# ARM_critter_v02.net
KiCad netlist of a schematic drawn in EAGLE
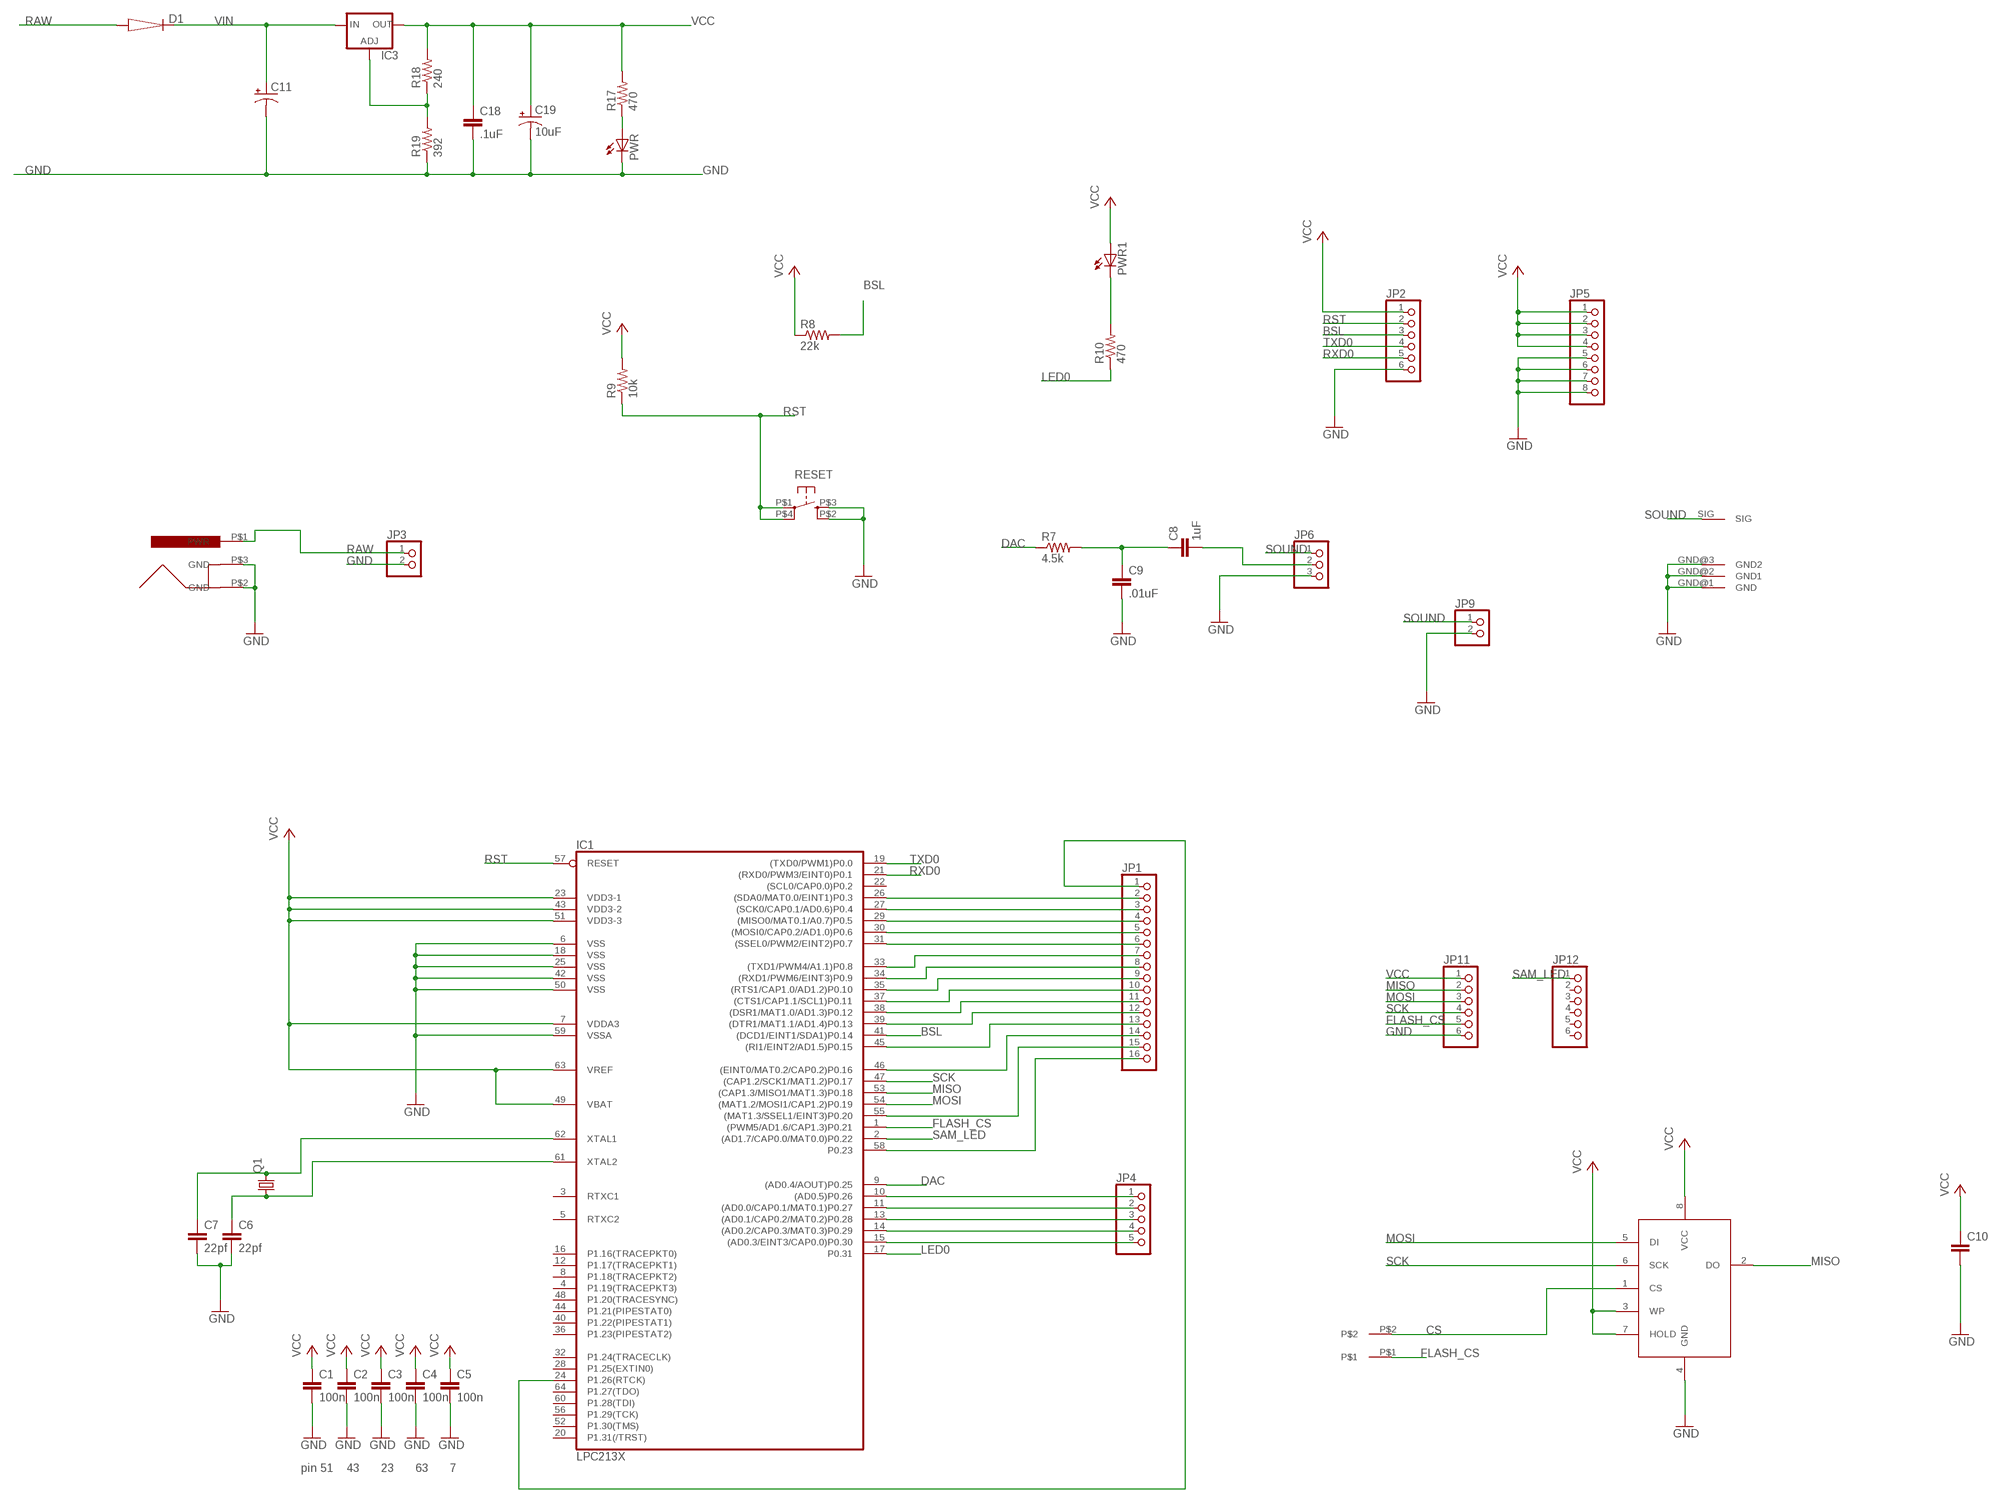
[diagram p0: schematic, sheet 1]

(export (version "E")
  (design (tool "Eeschema 10.0.6"))
  (components
    (comp (ref "C1")
      (value "100n")
      (footprint "eagle-import:C0603")
      (libsource (lib "eagle-import") (part "CAP0603"))
    )
    (comp (ref "C2")
      (value "100n")
      (footprint "eagle-import:C0603")
      (libsource (lib "eagle-import") (part "CAP0603"))
    )
    (comp (ref "C3")
      (value "100n")
      (footprint "eagle-import:C0603")
      (libsource (lib "eagle-import") (part "CAP0603"))
    )
    (comp (ref "C4")
      (value "100n")
      (footprint "eagle-import:C0603")
      (libsource (lib "eagle-import") (part "CAP0603"))
    )
    (comp (ref "C5")
      (value "100n")
      (footprint "eagle-import:C0603")
      (libsource (lib "eagle-import") (part "CAP0603"))
    )
    (comp (ref "C6")
      (value "22pf")
      (footprint "eagle-import:C0603")
      (libsource (lib "eagle-import") (part "CAP0603"))
    )
    (comp (ref "C7")
      (value "22pf")
      (footprint "eagle-import:C0603")
      (libsource (lib "eagle-import") (part "CAP0603"))
    )
    (comp (ref "C8")
      (value "1uF")
      (footprint "eagle-import:C0603")
      (libsource (lib "eagle-import") (part "CAP0603"))
    )
    (comp (ref "C9")
      (value ".01uF")
      (footprint "eagle-import:C0603")
      (libsource (lib "eagle-import") (part "CAP0603"))
    )
    (comp (ref "C10")
      (value "CAP0603")
      (footprint "eagle-import:C0603")
      (libsource (lib "eagle-import") (part "CAP0603"))
    )
    (comp (ref "C11")
      (value "CPOL-USE3.5-8")
      (footprint "eagle-import:E3,5-8")
      (libsource (lib "eagle-import") (part "CPOL-USE3.5-8"))
    )
    (comp (ref "C18")
      (value ".1uF")
      (footprint "eagle-import:C0603")
      (libsource (lib "eagle-import") (part "CAP0603"))
    )
    (comp (ref "C19")
      (value "10uF")
      (footprint "eagle-import:CPOL_1206")
      (libsource (lib "eagle-import") (part "CAP_POL1206"))
    )
    (comp (ref "D1")
      (value "DIODESMB")
      (footprint "eagle-import:SMB")
      (libsource (lib "eagle-import") (part "DIODESMB"))
    )
    (comp (ref "IC1")
      (value "LPC213X")
      (footprint "eagle-import:SQFP-S-10X10-64")
      (libsource (lib "eagle-import") (part "LPC213X"))
    )
    (comp (ref "IC3")
      (value "V_REG_FAN1117SOT223")
      (footprint "eagle-import:SOT223")
      (libsource (lib "eagle-import") (part "V_REG_FAN1117SOT223"))
    )
    (comp (ref "JP1")
      (value "PINHD-1X16")
      (footprint "eagle-import:1X16")
      (libsource (lib "eagle-import") (part "PINHD-1X16"))
    )
    (comp (ref "JP2")
      (value "PINHD-1X6")
      (footprint "eagle-import:1X06")
      (libsource (lib "eagle-import") (part "PINHD-1X6"))
    )
    (comp (ref "JP3")
      (value "PINHD-1X2")
      (footprint "eagle-import:1X02")
      (libsource (lib "eagle-import") (part "PINHD-1X2"))
    )
    (comp (ref "JP4")
      (value "PINHD-1X5")
      (footprint "eagle-import:1X05")
      (libsource (lib "eagle-import") (part "PINHD-1X5"))
    )
    (comp (ref "JP5")
      (value "PINHD-1X8")
      (footprint "eagle-import:1X08")
      (libsource (lib "eagle-import") (part "PINHD-1X8"))
    )
    (comp (ref "JP6")
      (value "PINHD-1X3")
      (footprint "eagle-import:1X03")
      (libsource (lib "eagle-import") (part "PINHD-1X3"))
    )
    (comp (ref "JP9")
      (value "PINHD-1X2")
      (footprint "eagle-import:1X02")
      (libsource (lib "eagle-import") (part "PINHD-1X2"))
    )
    (comp (ref "JP11")
      (value "PINHD-1X6")
      (footprint "eagle-import:1X06")
      (libsource (lib "eagle-import") (part "PINHD-1X6"))
    )
    (comp (ref "JP12")
      (value "PINHD-1X6")
      (footprint "eagle-import:1X06")
      (libsource (lib "eagle-import") (part "PINHD-1X6"))
    )
    (comp (ref "PWR")
      (value "LED1206")
      (footprint "eagle-import:CHIPLED_1206")
      (libsource (lib "eagle-import") (part "LED1206"))
    )
    (comp (ref "PWR1")
      (value "LED1206")
      (footprint "eagle-import:CHIPLED_1206")
      (libsource (lib "eagle-import") (part "LED1206"))
    )
    (comp (ref "Q1")
      (value "CRYSTALHC49UV")
      (footprint "eagle-import:HC49U-V")
      (libsource (lib "eagle-import") (part "CRYSTALHC49UV"))
    )
    (comp (ref "R7")
      (value "4.5k")
      (footprint "eagle-import:R0603")
      (libsource (lib "eagle-import") (part "RES0603"))
    )
    (comp (ref "R8")
      (value "22k")
      (footprint "eagle-import:R0603")
      (libsource (lib "eagle-import") (part "RES0603"))
    )
    (comp (ref "R9")
      (value "10k")
      (footprint "eagle-import:R0603")
      (libsource (lib "eagle-import") (part "RES0603"))
    )
    (comp (ref "R10")
      (value "470")
      (footprint "eagle-import:R0603")
      (libsource (lib "eagle-import") (part "RES0603"))
    )
    (comp (ref "R17")
      (value "470")
      (footprint "eagle-import:R0603")
      (libsource (lib "eagle-import") (part "RES0603"))
    )
    (comp (ref "R18")
      (value "240")
      (footprint "eagle-import:R0603")
      (libsource (lib "eagle-import") (part "RES0603"))
    )
    (comp (ref "R19")
      (value "392")
      (footprint "eagle-import:R0603")
      (libsource (lib "eagle-import") (part "RES0603"))
    )
    (comp (ref "RESET")
      (value "RESET_SWITCH")
      (footprint "eagle-import:TACTILE_SWITCH_SMD")
      (libsource (lib "eagle-import") (part "RESET_SWITCH"))
    )
    (comp (ref "U$1")
      (value "POWER_JACK")
      (footprint "eagle-import:POWER_JACK")
      (libsource (lib "eagle-import") (part "POWER_JACKTHRU-HOLE"))
    )
    (comp (ref "U$2")
      (value "M25PXX")
      (footprint "eagle-import:SO08")
      (libsource (lib "eagle-import") (part "M25PXX"))
    )
    (comp (ref "U$3")
      (value "JUMPER_SOL")
      (footprint "eagle-import:JUMPER_SOL")
      (libsource (lib "eagle-import") (part "JUMPER_SOL"))
    )
    (comp (ref "U$5")
      (value "PHONO_PLUG")
      (footprint "eagle-import:PHONO_PCB")
      (libsource (lib "eagle-import") (part "PHONO_PLUG"))
    )
  )
  (nets
    (net (code "1") (name "/BSL") (class "Default")
      (node (ref "IC1") (pin "41") (pinfunction "(DCD1/EINT1/SDA1)P0.14_41") (pintype "bidirectional"))
      (node (ref "JP2") (pin "3") (pinfunction "3_3") (pintype "passive"))
      (node (ref "R8") (pin "2") (pinfunction "2_2") (pintype "passive"))
    )
    (net (code "2") (name "/CS") (class "Default")
      (node (ref "U$2") (pin "1") (pinfunction "CS_1") (pintype "bidirectional"))
      (node (ref "U$3") (pin "P$2") (pinfunction "P$2_P$2") (pintype "bidirectional"))
    )
    (net (code "3") (name "/DAC") (class "Default")
      (node (ref "IC1") (pin "9") (pinfunction "(AD0.4/AOUT)P0.25_9") (pintype "bidirectional"))
      (node (ref "R7") (pin "1") (pinfunction "1_1") (pintype "passive"))
    )
    (net (code "4") (name "/FLASH_CS") (class "Default")
      (node (ref "IC1") (pin "1") (pinfunction "(PWM5/AD1.6/CAP1.3)P0.21_1") (pintype "bidirectional"))
      (node (ref "JP11") (pin "5") (pinfunction "5_5") (pintype "passive"))
      (node (ref "U$3") (pin "P$1") (pinfunction "P$1_P$1") (pintype "bidirectional"))
    )
    (net (code "5") (name "/LED0") (class "Default")
      (node (ref "IC1") (pin "17") (pinfunction "P0.31_17") (pintype "output"))
      (node (ref "R10") (pin "1") (pinfunction "1_1") (pintype "passive"))
    )
    (net (code "6") (name "/MISO") (class "Default")
      (node (ref "IC1") (pin "53") (pinfunction "(CAP1.3/MISO1/MAT1.3)P0.18_53") (pintype "bidirectional"))
      (node (ref "JP11") (pin "2") (pinfunction "2_2") (pintype "passive"))
      (node (ref "U$2") (pin "2") (pinfunction "DO_2") (pintype "bidirectional"))
    )
    (net (code "7") (name "/MOSI") (class "Default")
      (node (ref "IC1") (pin "54") (pinfunction "(MAT1.2/MOSI1/CAP1.2)P0.19_54") (pintype "bidirectional"))
      (node (ref "JP11") (pin "3") (pinfunction "3_3") (pintype "passive"))
      (node (ref "U$2") (pin "5") (pinfunction "DI_5") (pintype "bidirectional"))
    )
    (net (code "8") (name "/RAW") (class "Default")
      (node (ref "D1") (pin "2") (pinfunction "C_2") (pintype "passive"))
      (node (ref "JP3") (pin "1") (pinfunction "1_1") (pintype "passive"))
      (node (ref "U$1") (pin "P$1") (pinfunction "PWR_P$1") (pintype "bidirectional"))
    )
    (net (code "9") (name "/RST") (class "Default")
      (node (ref "IC1") (pin "57") (pinfunction "RESET_57") (pintype "input"))
      (node (ref "JP2") (pin "2") (pinfunction "2_2") (pintype "passive"))
      (node (ref "R9") (pin "1") (pinfunction "1_1") (pintype "passive"))
      (node (ref "RESET") (pin "P$1") (pinfunction "P_P$1") (pintype "passive"))
      (node (ref "RESET") (pin "P$4") (pinfunction "P1_P$4") (pintype "passive"))
    )
    (net (code "10") (name "/RXD0") (class "Default")
      (node (ref "IC1") (pin "21") (pinfunction "(RXD0/PWM3/EINT0)P0.1_21") (pintype "bidirectional"))
      (node (ref "JP2") (pin "5") (pinfunction "5_5") (pintype "passive"))
    )
    (net (code "11") (name "/SAM_LED") (class "Default")
      (node (ref "IC1") (pin "2") (pinfunction "(AD1.7/CAP0.0/MAT0.0)P0.22_2") (pintype "bidirectional"))
      (node (ref "JP12") (pin "1") (pinfunction "1_1") (pintype "passive"))
    )
    (net (code "12") (name "/SCK") (class "Default")
      (node (ref "IC1") (pin "47") (pinfunction "(CAP1.2/SCK1/MAT1.2)P0.17_47") (pintype "bidirectional"))
      (node (ref "JP11") (pin "4") (pinfunction "4_4") (pintype "passive"))
      (node (ref "U$2") (pin "6") (pinfunction "SCK_6") (pintype "bidirectional"))
    )
    (net (code "13") (name "/SOUND") (class "Default")
      (node (ref "JP6") (pin "1") (pinfunction "1_1") (pintype "passive"))
      (node (ref "JP9") (pin "1") (pinfunction "1_1") (pintype "passive"))
      (node (ref "U$5") (pin "SIG") (pinfunction "SIG_SIG") (pintype "bidirectional"))
    )
    (net (code "14") (name "/TXD0") (class "Default")
      (node (ref "IC1") (pin "19") (pinfunction "(TXD0/PWM1)P0.0_19") (pintype "bidirectional"))
      (node (ref "JP2") (pin "4") (pinfunction "4_4") (pintype "passive"))
    )
    (net (code "15") (name "/VIN") (class "Default")
      (node (ref "C11") (pin "+") (pinfunction "+_+") (pintype "passive"))
      (node (ref "D1") (pin "1") (pinfunction "A_1") (pintype "passive"))
      (node (ref "IC3") (pin "3") (pinfunction "IN_3") (pintype "input"))
    )
    (net (code "16") (name "GND") (class "Default")
      (node (ref "C1") (pin "2") (pinfunction "2_2") (pintype "passive"))
      (node (ref "C10") (pin "2") (pinfunction "2_2") (pintype "passive"))
      (node (ref "C11") (pin "-") (pinfunction "-_-") (pintype "passive"))
      (node (ref "C18") (pin "2") (pinfunction "2_2") (pintype "passive"))
      (node (ref "C19") (pin "C") (pinfunction "-_C") (pintype "passive"))
      (node (ref "C2") (pin "2") (pinfunction "2_2") (pintype "passive"))
      (node (ref "C3") (pin "2") (pinfunction "2_2") (pintype "passive"))
      (node (ref "C4") (pin "2") (pinfunction "2_2") (pintype "passive"))
      (node (ref "C5") (pin "2") (pinfunction "2_2") (pintype "passive"))
      (node (ref "C6") (pin "2") (pinfunction "2_2") (pintype "passive"))
      (node (ref "C7") (pin "2") (pinfunction "2_2") (pintype "passive"))
      (node (ref "C9") (pin "2") (pinfunction "2_2") (pintype "passive"))
      (node (ref "IC1") (pin "18") (pinfunction "VSS_18") (pintype "power_in"))
      (node (ref "IC1") (pin "25") (pinfunction "VSS_25") (pintype "power_in"))
      (node (ref "IC1") (pin "42") (pinfunction "VSS_42") (pintype "power_in"))
      (node (ref "IC1") (pin "50") (pinfunction "VSS_50") (pintype "power_in"))
      (node (ref "IC1") (pin "59") (pinfunction "VSSA_59") (pintype "power_in"))
      (node (ref "IC1") (pin "6") (pinfunction "VSS_6") (pintype "power_in"))
      (node (ref "JP11") (pin "6") (pinfunction "6_6") (pintype "passive"))
      (node (ref "JP2") (pin "6") (pinfunction "6_6") (pintype "passive"))
      (node (ref "JP3") (pin "2") (pinfunction "2_2") (pintype "passive"))
      (node (ref "JP5") (pin "5") (pinfunction "5_5") (pintype "passive"))
      (node (ref "JP5") (pin "6") (pinfunction "6_6") (pintype "passive"))
      (node (ref "JP5") (pin "7") (pinfunction "7_7") (pintype "passive"))
      (node (ref "JP5") (pin "8") (pinfunction "8_8") (pintype "passive"))
      (node (ref "JP6") (pin "3") (pinfunction "3_3") (pintype "passive"))
      (node (ref "JP9") (pin "2") (pinfunction "2_2") (pintype "passive"))
      (node (ref "PWR") (pin "C") (pinfunction "C_C") (pintype "passive"))
      (node (ref "R19") (pin "1") (pinfunction "1_1") (pintype "passive"))
      (node (ref "RESET") (pin "P$2") (pinfunction "S1_P$2") (pintype "passive"))
      (node (ref "RESET") (pin "P$3") (pinfunction "S_P$3") (pintype "passive"))
      (node (ref "U$1") (pin "P$2") (pinfunction "GND_P$2") (pintype "bidirectional"))
      (node (ref "U$1") (pin "P$3") (pinfunction "GND_P$3") (pintype "bidirectional"))
      (node (ref "U$2") (pin "4") (pinfunction "GND_4") (pintype "bidirectional"))
      (node (ref "U$5") (pin "GND@1") (pinfunction "GND_GND@1") (pintype "bidirectional"))
      (node (ref "U$5") (pin "GND@2") (pinfunction "GND1_GND@2") (pintype "bidirectional"))
      (node (ref "U$5") (pin "GND@3") (pinfunction "GND2_GND@3") (pintype "bidirectional"))
    )
    (net (code "17") (name "Net-(C8-Pad1)") (class "Default")
      (node (ref "C8") (pin "1") (pinfunction "1_1") (pintype "passive"))
      (node (ref "C9") (pin "1") (pinfunction "1_1") (pintype "passive"))
      (node (ref "R7") (pin "2") (pinfunction "2_2") (pintype "passive"))
    )
    (net (code "18") (name "Net-(C8-Pad2)") (class "Default")
      (node (ref "C8") (pin "2") (pinfunction "2_2") (pintype "passive"))
      (node (ref "JP6") (pin "2") (pinfunction "2_2") (pintype "passive"))
    )
    (net (code "19") (name "Net-(IC1-(AD0.0{slash}CAP0.1{slash}MAT0.1)P0.27)") (class "Default")
      (node (ref "IC1") (pin "11") (pinfunction "(AD0.0/CAP0.1/MAT0.1)P0.27_11") (pintype "bidirectional"))
      (node (ref "JP4") (pin "2") (pinfunction "2_2") (pintype "passive"))
    )
    (net (code "20") (name "Net-(IC1-(AD0.1{slash}CAP0.2{slash}MAT0.2)P0.28)") (class "Default")
      (node (ref "IC1") (pin "13") (pinfunction "(AD0.1/CAP0.2/MAT0.2)P0.28_13") (pintype "bidirectional"))
      (node (ref "JP4") (pin "3") (pinfunction "3_3") (pintype "passive"))
    )
    (net (code "21") (name "Net-(IC1-(AD0.2{slash}CAP0.3{slash}MAT0.3)P0.29)") (class "Default")
      (node (ref "IC1") (pin "14") (pinfunction "(AD0.2/CAP0.3/MAT0.3)P0.29_14") (pintype "bidirectional"))
      (node (ref "JP4") (pin "4") (pinfunction "4_4") (pintype "passive"))
    )
    (net (code "22") (name "Net-(IC1-(AD0.3{slash}EINT3{slash}CAP0.0)P0.30)") (class "Default")
      (node (ref "IC1") (pin "15") (pinfunction "(AD0.3/EINT3/CAP0.0)P0.30_15") (pintype "bidirectional"))
      (node (ref "JP4") (pin "5") (pinfunction "5_5") (pintype "passive"))
    )
    (net (code "23") (name "Net-(IC1-(AD0.5)P0.26)") (class "Default")
      (node (ref "IC1") (pin "10") (pinfunction "(AD0.5)P0.26_10") (pintype "bidirectional"))
      (node (ref "JP4") (pin "1") (pinfunction "1_1") (pintype "passive"))
    )
    (net (code "24") (name "Net-(IC1-(CTS1{slash}CAP1.1{slash}SCL1)P0.11)") (class "Default")
      (node (ref "IC1") (pin "37") (pinfunction "(CTS1/CAP1.1/SCL1)P0.11_37") (pintype "bidirectional"))
      (node (ref "JP1") (pin "10") (pinfunction "10_10") (pintype "passive"))
    )
    (net (code "25") (name "Net-(IC1-(DSR1{slash}MAT1.0{slash}AD1.3)P0.12)") (class "Default")
      (node (ref "IC1") (pin "38") (pinfunction "(DSR1/MAT1.0/AD1.3)P0.12_38") (pintype "bidirectional"))
      (node (ref "JP1") (pin "11") (pinfunction "11_11") (pintype "passive"))
    )
    (net (code "26") (name "Net-(IC1-(DTR1{slash}MAT1.1{slash}AD1.4)P0.13)") (class "Default")
      (node (ref "IC1") (pin "39") (pinfunction "(DTR1/MAT1.1/AD1.4)P0.13_39") (pintype "bidirectional"))
      (node (ref "JP1") (pin "12") (pinfunction "12_12") (pintype "passive"))
    )
    (net (code "27") (name "Net-(IC1-(EINT0{slash}MAT0.2{slash}CAP0.2)P0.16)") (class "Default")
      (node (ref "IC1") (pin "46") (pinfunction "(EINT0/MAT0.2/CAP0.2)P0.16_46") (pintype "bidirectional"))
      (node (ref "JP1") (pin "14") (pinfunction "14_14") (pintype "passive"))
    )
    (net (code "28") (name "Net-(IC1-(MAT1.3{slash}SSEL1{slash}EINT3)P0.20)") (class "Default")
      (node (ref "IC1") (pin "55") (pinfunction "(MAT1.3/SSEL1/EINT3)P0.20_55") (pintype "bidirectional"))
      (node (ref "JP1") (pin "15") (pinfunction "15_15") (pintype "passive"))
    )
    (net (code "29") (name "Net-(IC1-(MISO0{slash}MAT0.1{slash}A0.7)P0.5)") (class "Default")
      (node (ref "IC1") (pin "29") (pinfunction "(MISO0/MAT0.1/A0.7)P0.5_29") (pintype "bidirectional"))
      (node (ref "JP1") (pin "4") (pinfunction "4_4") (pintype "passive"))
    )
    (net (code "30") (name "Net-(IC1-(MOSI0{slash}CAP0.2{slash}AD1.0)P0.6)") (class "Default")
      (node (ref "IC1") (pin "30") (pinfunction "(MOSI0/CAP0.2/AD1.0)P0.6_30") (pintype "bidirectional"))
      (node (ref "JP1") (pin "5") (pinfunction "5_5") (pintype "passive"))
    )
    (net (code "31") (name "Net-(IC1-(RI1{slash}EINT2{slash}AD1.5)P0.15)") (class "Default")
      (node (ref "IC1") (pin "45") (pinfunction "(RI1/EINT2/AD1.5)P0.15_45") (pintype "bidirectional"))
      (node (ref "JP1") (pin "13") (pinfunction "13_13") (pintype "passive"))
    )
    (net (code "32") (name "Net-(IC1-(RTS1{slash}CAP1.0{slash}AD1.2)P0.10)") (class "Default")
      (node (ref "IC1") (pin "35") (pinfunction "(RTS1/CAP1.0/AD1.2)P0.10_35") (pintype "bidirectional"))
      (node (ref "JP1") (pin "9") (pinfunction "9_9") (pintype "passive"))
    )
    (net (code "33") (name "Net-(IC1-(RXD1{slash}PWM6{slash}EINT3)P0.9)") (class "Default")
      (node (ref "IC1") (pin "34") (pinfunction "(RXD1/PWM6/EINT3)P0.9_34") (pintype "bidirectional"))
      (node (ref "JP1") (pin "8") (pinfunction "8_8") (pintype "passive"))
    )
    (net (code "34") (name "Net-(IC1-(SCK0{slash}CAP0.1{slash}AD0.6)P0.4)") (class "Default")
      (node (ref "IC1") (pin "27") (pinfunction "(SCK0/CAP0.1/AD0.6)P0.4_27") (pintype "bidirectional"))
      (node (ref "JP1") (pin "3") (pinfunction "3_3") (pintype "passive"))
    )
    (net (code "35") (name "Net-(IC1-(SDA0{slash}MAT0.0{slash}EINT1)P0.3)") (class "Default")
      (node (ref "IC1") (pin "26") (pinfunction "(SDA0/MAT0.0/EINT1)P0.3_26") (pintype "bidirectional"))
      (node (ref "JP1") (pin "2") (pinfunction "2_2") (pintype "passive"))
    )
    (net (code "36") (name "Net-(IC1-(SSEL0{slash}PWM2{slash}EINT2)P0.7)") (class "Default")
      (node (ref "IC1") (pin "31") (pinfunction "(SSEL0/PWM2/EINT2)P0.7_31") (pintype "bidirectional"))
      (node (ref "JP1") (pin "6") (pinfunction "6_6") (pintype "passive"))
    )
    (net (code "37") (name "Net-(IC1-(TXD1{slash}PWM4{slash}A1.1)P0.8)") (class "Default")
      (node (ref "IC1") (pin "33") (pinfunction "(TXD1/PWM4/A1.1)P0.8_33") (pintype "bidirectional"))
      (node (ref "JP1") (pin "7") (pinfunction "7_7") (pintype "passive"))
    )
    (net (code "38") (name "Net-(IC1-P0.23)") (class "Default")
      (node (ref "IC1") (pin "58") (pinfunction "P0.23_58") (pintype "bidirectional"))
      (node (ref "JP1") (pin "16") (pinfunction "16_16") (pintype "passive"))
    )
    (net (code "39") (name "Net-(IC1-P1.26(RTCK))") (class "Default")
      (node (ref "IC1") (pin "24") (pinfunction "P1.26(RTCK)_24") (pintype "bidirectional"))
      (node (ref "JP1") (pin "1") (pinfunction "1_1") (pintype "passive"))
    )
    (net (code "40") (name "Net-(IC1-XTAL1)") (class "Default")
      (node (ref "C7") (pin "1") (pinfunction "1_1") (pintype "passive"))
      (node (ref "IC1") (pin "62") (pinfunction "XTAL1_62") (pintype "input"))
      (node (ref "Q1") (pin "2") (pinfunction "2_2") (pintype "passive"))
    )
    (net (code "41") (name "Net-(IC1-XTAL2)") (class "Default")
      (node (ref "C6") (pin "1") (pinfunction "1_1") (pintype "passive"))
      (node (ref "IC1") (pin "61") (pinfunction "XTAL2_61") (pintype "output"))
      (node (ref "Q1") (pin "1") (pinfunction "1_1") (pintype "passive"))
    )
    (net (code "42") (name "Net-(IC3-ADJ)") (class "Default")
      (node (ref "IC3") (pin "1") (pinfunction "ADJ_1") (pintype "input"))
      (node (ref "R18") (pin "1") (pinfunction "1_1") (pintype "passive"))
      (node (ref "R19") (pin "2") (pinfunction "2_2") (pintype "passive"))
    )
    (net (code "43") (name "Net-(PWR-PadA)") (class "Default")
      (node (ref "PWR") (pin "A") (pinfunction "A_A") (pintype "passive"))
      (node (ref "R17") (pin "1") (pinfunction "1_1") (pintype "passive"))
    )
    (net (code "44") (name "Net-(PWR1-PadC)") (class "Default")
      (node (ref "PWR1") (pin "C") (pinfunction "C_C") (pintype "passive"))
      (node (ref "R10") (pin "2") (pinfunction "2_2") (pintype "passive"))
    )
    (net (code "45") (name "VCC") (class "Default")
      (node (ref "C1") (pin "1") (pinfunction "1_1") (pintype "passive"))
      (node (ref "C10") (pin "1") (pinfunction "1_1") (pintype "passive"))
      (node (ref "C18") (pin "1") (pinfunction "1_1") (pintype "passive"))
      (node (ref "C19") (pin "A") (pinfunction "+_A") (pintype "passive"))
      (node (ref "C2") (pin "1") (pinfunction "1_1") (pintype "passive"))
      (node (ref "C3") (pin "1") (pinfunction "1_1") (pintype "passive"))
      (node (ref "C4") (pin "1") (pinfunction "1_1") (pintype "passive"))
      (node (ref "C5") (pin "1") (pinfunction "1_1") (pintype "passive"))
      (node (ref "IC1") (pin "23") (pinfunction "VDD3-1_23") (pintype "power_in"))
      (node (ref "IC1") (pin "43") (pinfunction "VDD3-2_43") (pintype "power_in"))
      (node (ref "IC1") (pin "49") (pinfunction "VBAT_49") (pintype "power_in"))
      (node (ref "IC1") (pin "51") (pinfunction "VDD3-3_51") (pintype "power_in"))
      (node (ref "IC1") (pin "63") (pinfunction "VREF_63") (pintype "input"))
      (node (ref "IC1") (pin "7") (pinfunction "VDDA3_7") (pintype "power_in"))
      (node (ref "IC3") (pin "2") (pinfunction "OUT_2") (pintype "passive"))
      (node (ref "JP11") (pin "1") (pinfunction "1_1") (pintype "passive"))
      (node (ref "JP2") (pin "1") (pinfunction "1_1") (pintype "passive"))
      (node (ref "JP5") (pin "1") (pinfunction "1_1") (pintype "passive"))
      (node (ref "JP5") (pin "2") (pinfunction "2_2") (pintype "passive"))
      (node (ref "JP5") (pin "3") (pinfunction "3_3") (pintype "passive"))
      (node (ref "JP5") (pin "4") (pinfunction "4_4") (pintype "passive"))
      (node (ref "PWR1") (pin "A") (pinfunction "A_A") (pintype "passive"))
      (node (ref "R17") (pin "2") (pinfunction "2_2") (pintype "passive"))
      (node (ref "R18") (pin "2") (pinfunction "2_2") (pintype "passive"))
      (node (ref "R8") (pin "1") (pinfunction "1_1") (pintype "passive"))
      (node (ref "R9") (pin "2") (pinfunction "2_2") (pintype "passive"))
      (node (ref "U$2") (pin "3") (pinfunction "WP_3") (pintype "bidirectional"))
      (node (ref "U$2") (pin "7") (pinfunction "HOLD_7") (pintype "bidirectional"))
      (node (ref "U$2") (pin "8") (pinfunction "VCC_8") (pintype "bidirectional"))
    )
    (net (code "46") (name "unconnected-(IC1-(SCL0{slash}CAP0.0)P0.2-Pad22)") (class "Default")
      (node (ref "IC1") (pin "22") (pinfunction "(SCL0/CAP0.0)P0.2_22") (pintype "bidirectional"))
    )
    (net (code "47") (name "unconnected-(IC1-P1.16(TRACEPKT0)-Pad16)") (class "Default")
      (node (ref "IC1") (pin "16") (pinfunction "P1.16(TRACEPKT0)_16") (pintype "bidirectional"))
    )
    (net (code "48") (name "unconnected-(IC1-P1.17(TRACEPKT1)-Pad12)") (class "Default")
      (node (ref "IC1") (pin "12") (pinfunction "P1.17(TRACEPKT1)_12") (pintype "bidirectional"))
    )
    (net (code "49") (name "unconnected-(IC1-P1.18(TRACEPKT2)-Pad8)") (class "Default")
      (node (ref "IC1") (pin "8") (pinfunction "P1.18(TRACEPKT2)_8") (pintype "bidirectional"))
    )
    (net (code "50") (name "unconnected-(IC1-P1.19(TRACEPKT3)-Pad4)") (class "Default")
      (node (ref "IC1") (pin "4") (pinfunction "P1.19(TRACEPKT3)_4") (pintype "bidirectional"))
    )
    (net (code "51") (name "unconnected-(IC1-P1.20(TRACESYNC)-Pad48)") (class "Default")
      (node (ref "IC1") (pin "48") (pinfunction "P1.20(TRACESYNC)_48") (pintype "bidirectional"))
    )
    (net (code "52") (name "unconnected-(IC1-P1.21(PIPESTAT0)-Pad44)") (class "Default")
      (node (ref "IC1") (pin "44") (pinfunction "P1.21(PIPESTAT0)_44") (pintype "bidirectional"))
    )
    (net (code "53") (name "unconnected-(IC1-P1.22(PIPESTAT1)-Pad40)") (class "Default")
      (node (ref "IC1") (pin "40") (pinfunction "P1.22(PIPESTAT1)_40") (pintype "bidirectional"))
    )
    (net (code "54") (name "unconnected-(IC1-P1.23(PIPESTAT2)-Pad36)") (class "Default")
      (node (ref "IC1") (pin "36") (pinfunction "P1.23(PIPESTAT2)_36") (pintype "bidirectional"))
    )
    (net (code "55") (name "unconnected-(IC1-P1.24(TRACECLK)-Pad32)") (class "Default")
      (node (ref "IC1") (pin "32") (pinfunction "P1.24(TRACECLK)_32") (pintype "bidirectional"))
    )
    (net (code "56") (name "unconnected-(IC1-P1.25(EXTIN0)-Pad28)") (class "Default")
      (node (ref "IC1") (pin "28") (pinfunction "P1.25(EXTIN0)_28") (pintype "bidirectional"))
    )
    (net (code "57") (name "unconnected-(IC1-P1.27(TDO)-Pad64)") (class "Default")
      (node (ref "IC1") (pin "64") (pinfunction "P1.27(TDO)_64") (pintype "bidirectional"))
    )
    (net (code "58") (name "unconnected-(IC1-P1.28(TDI)-Pad60)") (class "Default")
      (node (ref "IC1") (pin "60") (pinfunction "P1.28(TDI)_60") (pintype "bidirectional"))
    )
    (net (code "59") (name "unconnected-(IC1-P1.29(TCK)-Pad56)") (class "Default")
      (node (ref "IC1") (pin "56") (pinfunction "P1.29(TCK)_56") (pintype "bidirectional"))
    )
    (net (code "60") (name "unconnected-(IC1-P1.30(TMS)-Pad52)") (class "Default")
      (node (ref "IC1") (pin "52") (pinfunction "P1.30(TMS)_52") (pintype "bidirectional"))
    )
    (net (code "61") (name "unconnected-(IC1-P1.31({slash}TRST)-Pad20)") (class "Default")
      (node (ref "IC1") (pin "20") (pinfunction "P1.31(/TRST)_20") (pintype "bidirectional"))
    )
    (net (code "62") (name "unconnected-(IC1-RTXC1-Pad3)") (class "Default")
      (node (ref "IC1") (pin "3") (pinfunction "RTXC1_3") (pintype "input"))
    )
    (net (code "63") (name "unconnected-(IC1-RTXC2-Pad5)") (class "Default")
      (node (ref "IC1") (pin "5") (pinfunction "RTXC2_5") (pintype "output"))
    )
    (net (code "64") (name "unconnected-(JP12-Pad2)") (class "Default")
      (node (ref "JP12") (pin "2") (pinfunction "2_2") (pintype "passive"))
    )
    (net (code "65") (name "unconnected-(JP12-Pad3)") (class "Default")
      (node (ref "JP12") (pin "3") (pinfunction "3_3") (pintype "passive"))
    )
    (net (code "66") (name "unconnected-(JP12-Pad4)") (class "Default")
      (node (ref "JP12") (pin "4") (pinfunction "4_4") (pintype "passive"))
    )
    (net (code "67") (name "unconnected-(JP12-Pad5)") (class "Default")
      (node (ref "JP12") (pin "5") (pinfunction "5_5") (pintype "passive"))
    )
    (net (code "68") (name "unconnected-(JP12-Pad6)") (class "Default")
      (node (ref "JP12") (pin "6") (pinfunction "6_6") (pintype "passive"))
    )
  )
)
